# 4_1.net
KiCad netlist of a schematic drawn in Altium Designer
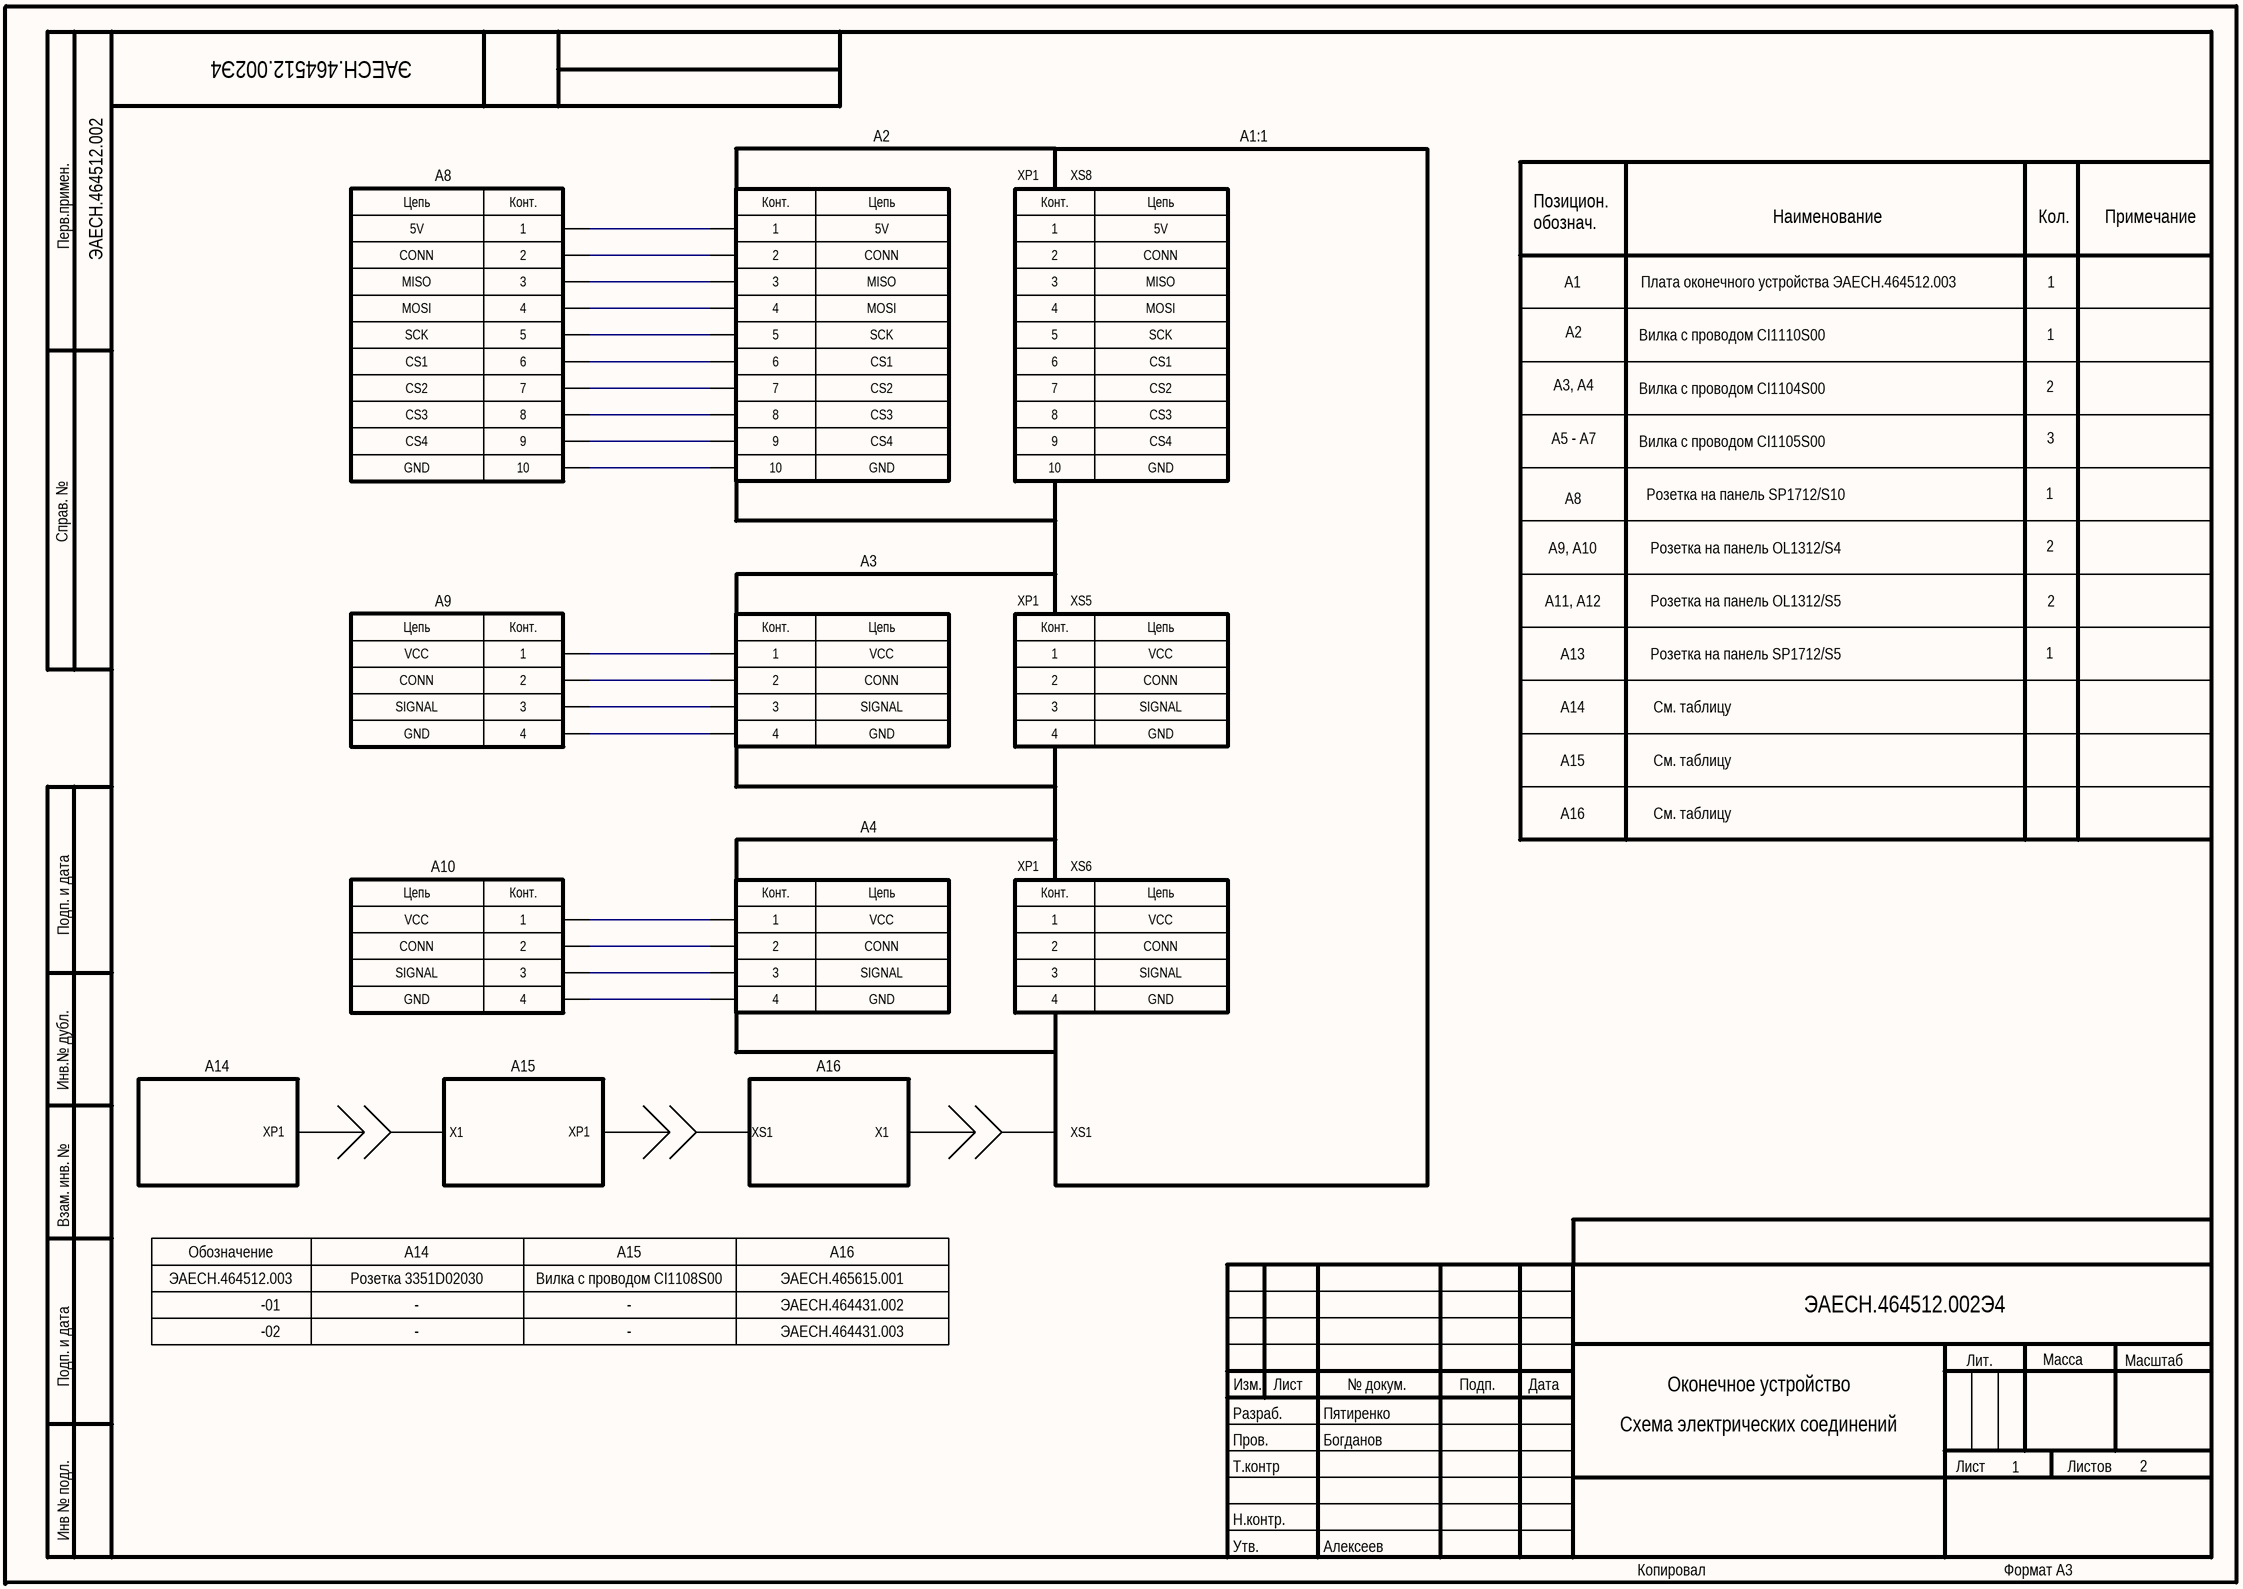
[diagram p0: Э4_1.SchDoc]

(export (version "E")
  (design (tool "Eeschema 10.0.6"))
  (components
    (comp (ref "X4") (value "10pin") (libsource (lib "Schlib1") (part "10pin")))
    (comp (ref "X5") (value "10pin") (libsource (lib "Schlib1") (part "10pin")))
    (comp (ref "X6") (value "10pin_con") (libsource (lib "Schlib1") (part "10pin_con")))
    (comp (ref "X10") (value "4pin") (libsource (lib "Schlib1") (part "4pin")))
    (comp (ref "X11") (value "4pin") (libsource (lib "Schlib1") (part "4pin")))
    (comp (ref "X12") (value "4pin_con") (libsource (lib "Schlib1") (part "4pin_con")))
    (comp (ref "X16") (value "4pin") (libsource (lib "Schlib1") (part "4pin")))
    (comp (ref "X17") (value "4pin") (libsource (lib "Schlib1") (part "4pin")))
    (comp (ref "X18") (value "4pin_con") (libsource (lib "Schlib1") (part "4pin_con")))
  )
  (nets
    (net (code "1") (name "Net-(X4-Pad1)") (class "Default")
      (node (ref "X4") (pin "1") (pinfunction "1_1") (pintype "passive"))
      (node (ref "X5") (pin "1") (pinfunction "1_1") (pintype "passive"))
    )
    (net (code "2") (name "Net-(X4-Pad1)_1") (class "Default")
      (node (ref "X4") (pin "1") (pinfunction "1_1") (pintype "passive"))
      (node (ref "X5") (pin "1") (pinfunction "1_1") (pintype "passive"))
    )
    (net (code "3") (name "Net-(X4-Pad2)") (class "Default")
      (node (ref "X4") (pin "2") (pinfunction "2_2") (pintype "passive"))
      (node (ref "X5") (pin "2") (pinfunction "2_2") (pintype "passive"))
    )
    (net (code "4") (name "Net-(X4-Pad2)_1") (class "Default")
      (node (ref "X4") (pin "2") (pinfunction "2_2") (pintype "passive"))
      (node (ref "X5") (pin "2") (pinfunction "2_2") (pintype "passive"))
    )
    (net (code "5") (name "Net-(X4-Pad3)") (class "Default")
      (node (ref "X4") (pin "3") (pinfunction "3_3") (pintype "passive"))
      (node (ref "X5") (pin "3") (pinfunction "3_3") (pintype "passive"))
    )
    (net (code "6") (name "Net-(X4-Pad3)_1") (class "Default")
      (node (ref "X4") (pin "3") (pinfunction "3_3") (pintype "passive"))
      (node (ref "X5") (pin "3") (pinfunction "3_3") (pintype "passive"))
    )
    (net (code "7") (name "Net-(X4-Pad4)") (class "Default")
      (node (ref "X4") (pin "4") (pinfunction "4_4") (pintype "passive"))
      (node (ref "X5") (pin "4") (pinfunction "4_4") (pintype "passive"))
    )
    (net (code "8") (name "Net-(X4-Pad4)_1") (class "Default")
      (node (ref "X4") (pin "4") (pinfunction "4_4") (pintype "passive"))
      (node (ref "X5") (pin "4") (pinfunction "4_4") (pintype "passive"))
    )
    (net (code "9") (name "Net-(X4-Pad4)_2") (class "Default")
      (node (ref "X4") (pin "4") (pinfunction "4_4") (pintype "passive"))
      (node (ref "X5") (pin "4") (pinfunction "4_4") (pintype "passive"))
    )
    (net (code "10") (name "Net-(X4-Pad4)_3") (class "Default")
      (node (ref "X4") (pin "4") (pinfunction "4_4") (pintype "passive"))
      (node (ref "X5") (pin "4") (pinfunction "4_4") (pintype "passive"))
    )
    (net (code "11") (name "Net-(X10-Pad1)") (class "Default")
      (node (ref "X10") (pin "1") (pinfunction "1_1") (pintype "passive"))
      (node (ref "X11") (pin "1") (pinfunction "1_1") (pintype "passive"))
    )
    (net (code "12") (name "Net-(X10-Pad2)") (class "Default")
      (node (ref "X10") (pin "2") (pinfunction "2_2") (pintype "passive"))
      (node (ref "X11") (pin "2") (pinfunction "2_2") (pintype "passive"))
    )
    (net (code "13") (name "Net-(X10-Pad3)") (class "Default")
      (node (ref "X10") (pin "3") (pinfunction "3_3") (pintype "passive"))
      (node (ref "X11") (pin "3") (pinfunction "3_3") (pintype "passive"))
    )
    (net (code "14") (name "Net-(X10-Pad4)") (class "Default")
      (node (ref "X10") (pin "4") (pinfunction "4_4") (pintype "passive"))
      (node (ref "X11") (pin "4") (pinfunction "4_4") (pintype "passive"))
    )
    (net (code "15") (name "Net-(X16-Pad1)") (class "Default")
      (node (ref "X16") (pin "1") (pinfunction "1_1") (pintype "passive"))
      (node (ref "X17") (pin "1") (pinfunction "1_1") (pintype "passive"))
    )
    (net (code "16") (name "Net-(X16-Pad2)") (class "Default")
      (node (ref "X16") (pin "2") (pinfunction "2_2") (pintype "passive"))
      (node (ref "X17") (pin "2") (pinfunction "2_2") (pintype "passive"))
    )
    (net (code "17") (name "Net-(X16-Pad3)") (class "Default")
      (node (ref "X16") (pin "3") (pinfunction "3_3") (pintype "passive"))
      (node (ref "X17") (pin "3") (pinfunction "3_3") (pintype "passive"))
    )
    (net (code "18") (name "Net-(X16-Pad4)") (class "Default")
      (node (ref "X16") (pin "4") (pinfunction "4_4") (pintype "passive"))
      (node (ref "X17") (pin "4") (pinfunction "4_4") (pintype "passive"))
    )
  )
)
